# 4BitCounter.net
KiCad netlist of a schematic drawn in EAGLE
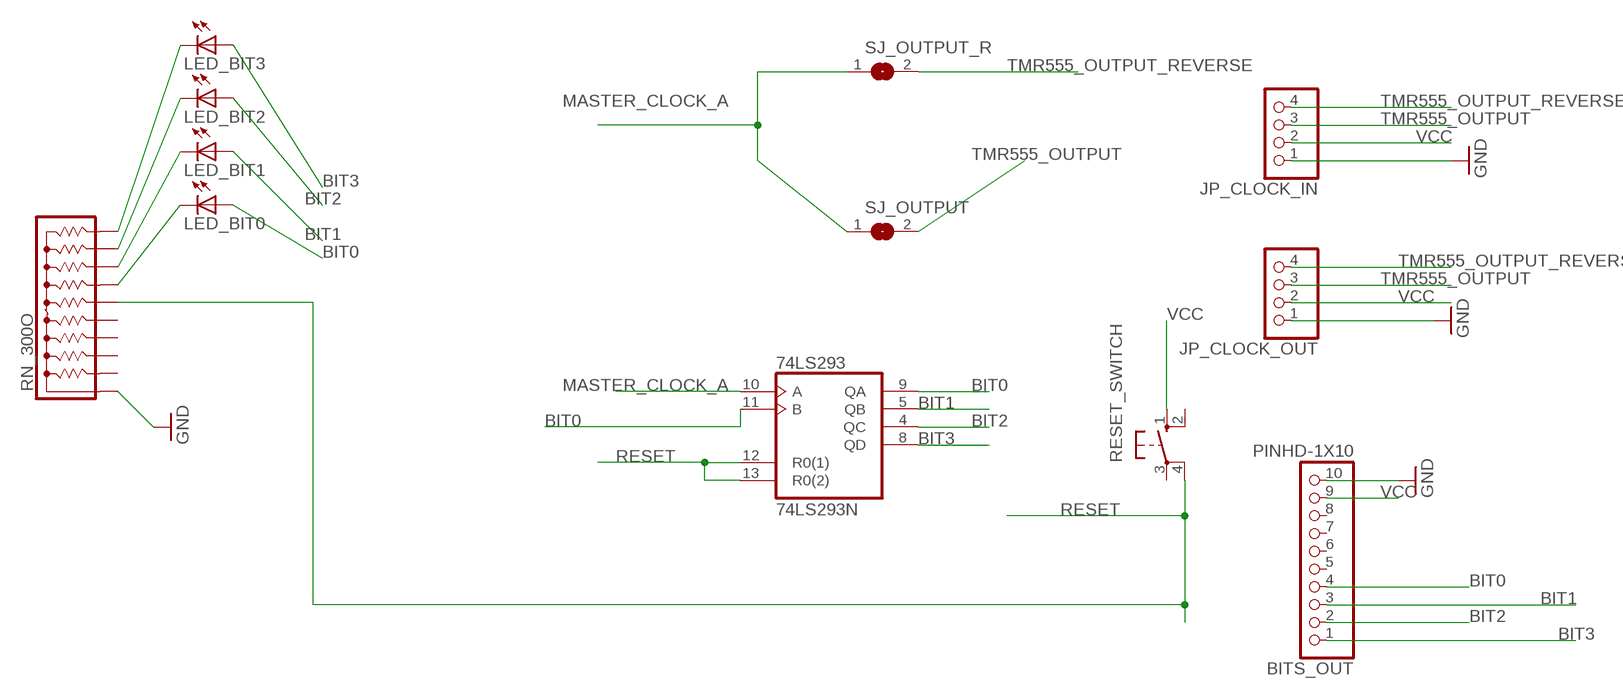
[diagram p0: schematic, sheet 1]

(export (version "E")
  (design (tool "Eeschema 10.0.6"))
  (components
    (comp (ref "74LS293")
      (value "74LS293N")
      (footprint "eagle-import:DIL14")
      (libsource (lib "eagle-import") (part "74293NLS"))
    )
    (comp (ref "BITS_OUT")
      (value "PINHD-1X10")
      (footprint "eagle-import:1X10-BIG")
      (libsource (lib "eagle-import") (part "PINHD-1X10"))
    )
    (comp (ref "JP_CLOCK_IN")
      (value "PINHD-1X4")
      (footprint "eagle-import:1X04")
      (libsource (lib "eagle-import") (part "PINHD-1X4"))
    )
    (comp (ref "JP_CLOCK_OUT")
      (value "PINHD-1X4")
      (footprint "eagle-import:1X04")
      (libsource (lib "eagle-import") (part "PINHD-1X4"))
    )
    (comp (ref "LED_BIT0")
      (value "LEDSMT1206")
      (footprint "eagle-import:1206")
      (libsource (lib "eagle-import") (part "LEDSMT1206"))
    )
    (comp (ref "LED_BIT1")
      (value "LEDSMT1206")
      (footprint "eagle-import:1206")
      (libsource (lib "eagle-import") (part "LEDSMT1206"))
    )
    (comp (ref "LED_BIT2")
      (value "LEDSMT1206")
      (footprint "eagle-import:1206")
      (libsource (lib "eagle-import") (part "LEDSMT1206"))
    )
    (comp (ref "LED_BIT3")
      (value "LEDSMT1206")
      (footprint "eagle-import:1206")
      (libsource (lib "eagle-import") (part "LEDSMT1206"))
    )
    (comp (ref "RESET_SWITCH")
      (value "10-XX")
      (footprint "eagle-import:B3F-10XX")
      (fields (field (name "MPN") "B3F-1000"))
      (libsource (lib "eagle-import") (part "10-XX"))
    )
    (comp (ref "RN_300O")
      (value "4610X")
      (footprint "eagle-import:SIP10")
      (libsource (lib "eagle-import") (part "4610X"))
    )
    (comp (ref "SJ_OUTPUT")
      (value "SOLDERJUMPERREFLOW")
      (footprint "eagle-import:SOLDERJUMPER_REFLOW")
      (libsource (lib "eagle-import") (part "SOLDERJUMPERREFLOW"))
    )
    (comp (ref "SJ_OUTPUT_R")
      (value "SOLDERJUMPERREFLOW")
      (footprint "eagle-import:SOLDERJUMPER_REFLOW")
      (libsource (lib "eagle-import") (part "SOLDERJUMPERREFLOW"))
    )
  )
  (nets
    (net (code "1") (name "/BIT0") (class "Default")
      (node (ref "74LS293") (pin "11") (pinfunction "B_11") (pintype "input"))
      (node (ref "74LS293") (pin "9") (pinfunction "QA_9") (pintype "output"))
      (node (ref "BITS_OUT") (pin "4") (pinfunction "4_4") (pintype "passive"))
      (node (ref "LED_BIT0") (pin "A") (pinfunction "A_A") (pintype "passive"))
    )
    (net (code "2") (name "/BIT1") (class "Default")
      (node (ref "74LS293") (pin "5") (pinfunction "QB_5") (pintype "output"))
      (node (ref "BITS_OUT") (pin "3") (pinfunction "3_3") (pintype "passive"))
      (node (ref "LED_BIT1") (pin "A") (pinfunction "A_A") (pintype "passive"))
    )
    (net (code "3") (name "/BIT2") (class "Default")
      (node (ref "74LS293") (pin "4") (pinfunction "QC_4") (pintype "output"))
      (node (ref "BITS_OUT") (pin "2") (pinfunction "2_2") (pintype "passive"))
      (node (ref "LED_BIT2") (pin "A") (pinfunction "A_A") (pintype "passive"))
    )
    (net (code "4") (name "/BIT3") (class "Default")
      (node (ref "74LS293") (pin "8") (pinfunction "QD_8") (pintype "output"))
      (node (ref "BITS_OUT") (pin "1") (pinfunction "1_1") (pintype "passive"))
      (node (ref "LED_BIT3") (pin "A") (pinfunction "A_A") (pintype "passive"))
    )
    (net (code "5") (name "/MASTER_CLOCK_A") (class "Default")
      (node (ref "74LS293") (pin "10") (pinfunction "A_10") (pintype "input"))
      (node (ref "SJ_OUTPUT") (pin "1") (pinfunction "1_1") (pintype "passive"))
      (node (ref "SJ_OUTPUT_R") (pin "1") (pinfunction "1_1") (pintype "passive"))
    )
    (net (code "6") (name "/RESET") (class "Default")
      (node (ref "74LS293") (pin "12") (pinfunction "R0(1)_12") (pintype "input"))
      (node (ref "74LS293") (pin "13") (pinfunction "R0(2)_13") (pintype "input"))
      (node (ref "RESET_SWITCH") (pin "4") (pinfunction "P1_4") (pintype "passive"))
      (node (ref "RN_300O") (pin "6") (pinfunction "6_6") (pintype "passive"))
    )
    (net (code "7") (name "/TMR555_OUTPUT") (class "Default")
      (node (ref "JP_CLOCK_IN") (pin "3") (pinfunction "3_3") (pintype "passive"))
      (node (ref "JP_CLOCK_OUT") (pin "3") (pinfunction "3_3") (pintype "passive"))
      (node (ref "SJ_OUTPUT") (pin "2") (pinfunction "2_2") (pintype "passive"))
    )
    (net (code "8") (name "/TMR555_OUTPUT_REVERSE") (class "Default")
      (node (ref "JP_CLOCK_IN") (pin "4") (pinfunction "4_4") (pintype "passive"))
      (node (ref "JP_CLOCK_OUT") (pin "4") (pinfunction "4_4") (pintype "passive"))
      (node (ref "SJ_OUTPUT_R") (pin "2") (pinfunction "2_2") (pintype "passive"))
    )
    (net (code "9") (name "/VCC") (class "Default")
      (node (ref "BITS_OUT") (pin "9") (pinfunction "9_9") (pintype "passive"))
      (node (ref "JP_CLOCK_IN") (pin "2") (pinfunction "2_2") (pintype "passive"))
      (node (ref "JP_CLOCK_OUT") (pin "2") (pinfunction "2_2") (pintype "passive"))
      (node (ref "RESET_SWITCH") (pin "1") (pinfunction "S_1") (pintype "passive"))
    )
    (net (code "10") (name "GND") (class "Default")
      (node (ref "BITS_OUT") (pin "10") (pinfunction "10_10") (pintype "passive"))
      (node (ref "JP_CLOCK_IN") (pin "1") (pinfunction "1_1") (pintype "passive"))
      (node (ref "JP_CLOCK_OUT") (pin "1") (pinfunction "1_1") (pintype "passive"))
      (node (ref "RN_300O") (pin "1") (pinfunction "1_1") (pintype "passive"))
    )
    (net (code "11") (name "Net-(LED_BIT0-PadC)") (class "Default")
      (node (ref "LED_BIT0") (pin "C") (pinfunction "C_C") (pintype "passive"))
      (node (ref "RN_300O") (pin "7") (pinfunction "7_7") (pintype "passive"))
    )
    (net (code "12") (name "Net-(LED_BIT1-PadC)") (class "Default")
      (node (ref "LED_BIT1") (pin "C") (pinfunction "C_C") (pintype "passive"))
      (node (ref "RN_300O") (pin "8") (pinfunction "8_8") (pintype "passive"))
    )
    (net (code "13") (name "Net-(LED_BIT2-PadC)") (class "Default")
      (node (ref "LED_BIT2") (pin "C") (pinfunction "C_C") (pintype "passive"))
      (node (ref "RN_300O") (pin "9") (pinfunction "9_9") (pintype "passive"))
    )
    (net (code "14") (name "Net-(LED_BIT3-PadC)") (class "Default")
      (node (ref "LED_BIT3") (pin "C") (pinfunction "C_C") (pintype "passive"))
      (node (ref "RN_300O") (pin "10") (pinfunction "10_10") (pintype "passive"))
    )
    (net (code "15") (name "unconnected-(BITS_OUT-Pad5)") (class "Default")
      (node (ref "BITS_OUT") (pin "5") (pinfunction "5_5") (pintype "passive"))
    )
    (net (code "16") (name "unconnected-(BITS_OUT-Pad6)") (class "Default")
      (node (ref "BITS_OUT") (pin "6") (pinfunction "6_6") (pintype "passive"))
    )
    (net (code "17") (name "unconnected-(BITS_OUT-Pad7)") (class "Default")
      (node (ref "BITS_OUT") (pin "7") (pinfunction "7_7") (pintype "passive"))
    )
    (net (code "18") (name "unconnected-(BITS_OUT-Pad8)") (class "Default")
      (node (ref "BITS_OUT") (pin "8") (pinfunction "8_8") (pintype "passive"))
    )
    (net (code "19") (name "unconnected-(RESET_SWITCH-P-Pad3)") (class "Default")
      (node (ref "RESET_SWITCH") (pin "3") (pinfunction "P_3") (pintype "passive"))
    )
    (net (code "20") (name "unconnected-(RESET_SWITCH-S1-Pad2)") (class "Default")
      (node (ref "RESET_SWITCH") (pin "2") (pinfunction "S1_2") (pintype "passive"))
    )
    (net (code "21") (name "unconnected-(RN_300O-Pad2)") (class "Default")
      (node (ref "RN_300O") (pin "2") (pinfunction "2_2") (pintype "passive"))
    )
    (net (code "22") (name "unconnected-(RN_300O-Pad3)") (class "Default")
      (node (ref "RN_300O") (pin "3") (pinfunction "3_3") (pintype "passive"))
    )
    (net (code "23") (name "unconnected-(RN_300O-Pad4)") (class "Default")
      (node (ref "RN_300O") (pin "4") (pinfunction "4_4") (pintype "passive"))
    )
    (net (code "24") (name "unconnected-(RN_300O-Pad5)") (class "Default")
      (node (ref "RN_300O") (pin "5") (pinfunction "5_5") (pintype "passive"))
    )
  )
)
